# working.net
KiCad netlist of a schematic drawn in EAGLE
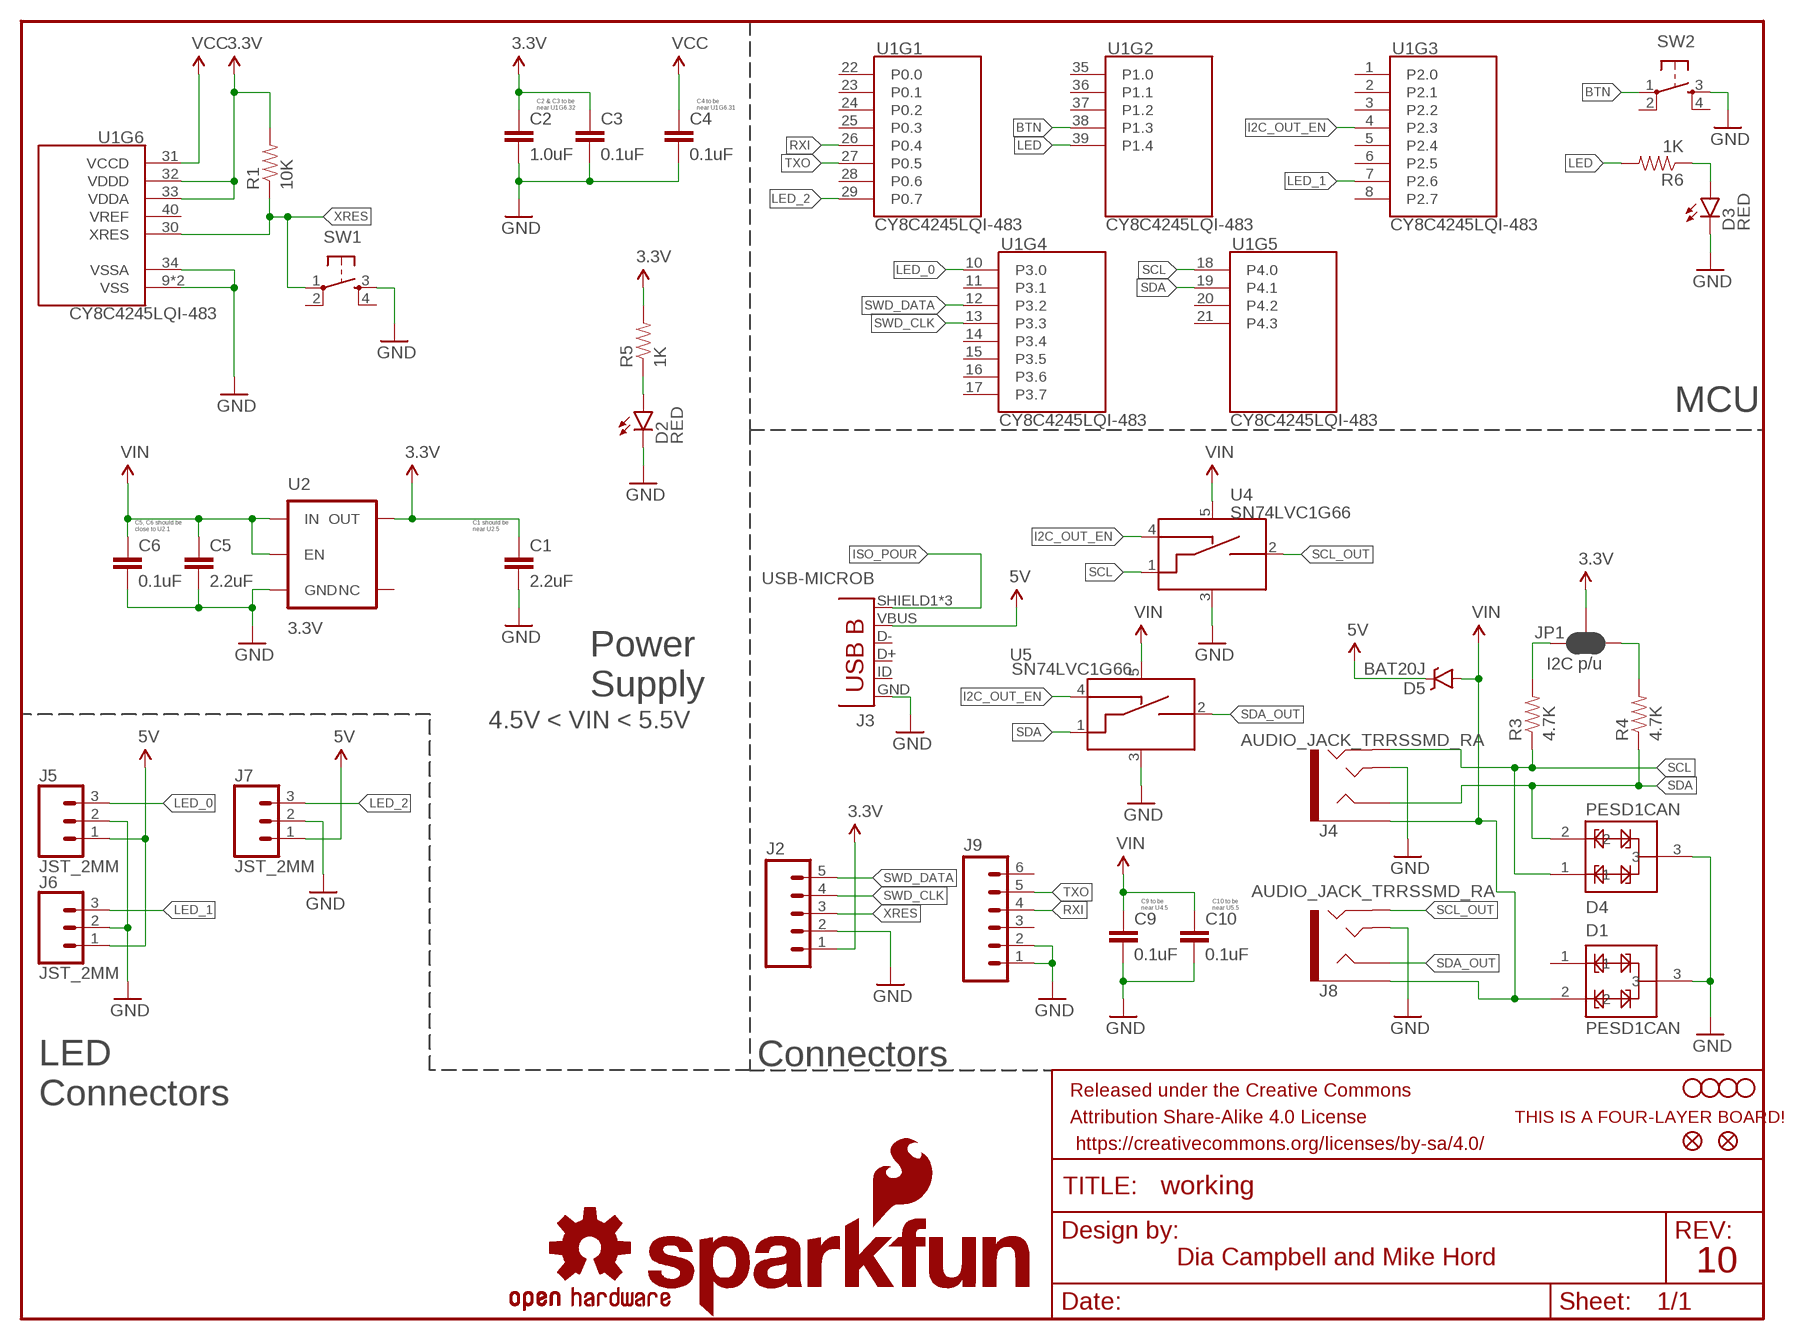
[diagram p0: schematic, sheet 1]

(export (version "E")
  (design (tool "Eeschema 10.0.6"))
  (components
    (comp (ref "C1")
      (value "2.2uF")
      (footprint "eagle-import:0603-CAP")
      (libsource (lib "eagle-import") (part "2.2UF-10V-20%(0603)"))
    )
    (comp (ref "C2")
      (value "1.0uF")
      (footprint "eagle-import:0402-CAP")
      (libsource (lib "eagle-import") (part "1.0UF-16V-10%(0402)"))
    )
    (comp (ref "C3")
      (value "0.1uF")
      (footprint "eagle-import:0402-CAP")
      (libsource (lib "eagle-import") (part "0.1UF-16V(+-10%)(0402)"))
    )
    (comp (ref "C4")
      (value "0.1uF")
      (footprint "eagle-import:0402-CAP")
      (libsource (lib "eagle-import") (part "0.1UF-16V(+-10%)(0402)"))
    )
    (comp (ref "C5")
      (value "2.2uF")
      (footprint "eagle-import:0603-CAP")
      (libsource (lib "eagle-import") (part "2.2UF-10V-20%(0603)"))
    )
    (comp (ref "C6")
      (value "0.1uF")
      (footprint "eagle-import:0402-CAP")
      (libsource (lib "eagle-import") (part "0.1UF-16V(+-10%)(0402)"))
    )
    (comp (ref "C9")
      (value "0.1uF")
      (footprint "eagle-import:0402-CAP")
      (libsource (lib "eagle-import") (part "0.1UF-16V(+-10%)(0402)"))
    )
    (comp (ref "C10")
      (value "0.1uF")
      (footprint "eagle-import:0402-CAP")
      (libsource (lib "eagle-import") (part "0.1UF-16V(+-10%)(0402)"))
    )
    (comp (ref "D1")
      (value "PESD1CAN")
      (footprint "eagle-import:SOT23-3")
      (libsource (lib "eagle-import") (part "PESD1CAN"))
    )
    (comp (ref "D2")
      (value "RED")
      (footprint "eagle-import:LED-0603")
      (libsource (lib "eagle-import") (part "LED-RED0603"))
    )
    (comp (ref "D3")
      (value "RED")
      (footprint "eagle-import:LED-0603")
      (libsource (lib "eagle-import") (part "LED-RED0603"))
    )
    (comp (ref "D4")
      (value "PESD1CAN")
      (footprint "eagle-import:SOT23-3")
      (libsource (lib "eagle-import") (part "PESD1CAN"))
    )
    (comp (ref "D5")
      (value "BAT20J")
      (footprint "eagle-import:SOD-323")
      (libsource (lib "eagle-import") (part "DIODE-SCHOTTKY-BAT20J"))
    )
    (comp (ref "FD1")
      (value "FIDUCIALUFIDUCIAL")
      (footprint "eagle-import:MICRO-FIDUCIAL")
      (libsource (lib "eagle-import") (part "FIDUCIALUFIDUCIAL"))
    )
    (comp (ref "FD2")
      (value "FIDUCIALUFIDUCIAL")
      (footprint "eagle-import:MICRO-FIDUCIAL")
      (libsource (lib "eagle-import") (part "FIDUCIALUFIDUCIAL"))
    )
    (comp (ref "FRAME1")
      (value "FRAME-LETTER")
      (footprint "eagle-import:CREATIVE_COMMONS")
      (libsource (lib "eagle-import") (part "FRAME-LETTER"))
    )
    (comp (ref "H1")
      (value "STAND-OFF")
      (footprint "eagle-import:STAND-OFF")
      (libsource (lib "eagle-import") (part "STAND-OFF"))
    )
    (comp (ref "H2")
      (value "STAND-OFF")
      (footprint "eagle-import:STAND-OFF")
      (libsource (lib "eagle-import") (part "STAND-OFF"))
    )
    (comp (ref "H3")
      (value "STAND-OFF")
      (footprint "eagle-import:STAND-OFF")
      (libsource (lib "eagle-import") (part "STAND-OFF"))
    )
    (comp (ref "H4")
      (value "STAND-OFF")
      (footprint "eagle-import:STAND-OFF")
      (libsource (lib "eagle-import") (part "STAND-OFF"))
    )
    (comp (ref "J2")
      (value "M05NO_SILK")
      (footprint "eagle-import:1X05_NO_SILK")
      (libsource (lib "eagle-import") (part "M05NO_SILK"))
    )
    (comp (ref "J3")
      (value "USB-MICROB")
      (footprint "eagle-import:USB-B-MICRO-SMD_V03")
      (libsource (lib "eagle-import") (part "USB-MICROB{dblquote}"))
    )
    (comp (ref "J4")
      (value "AUDIO_JACK_TRRSSMD_RA")
      (footprint "eagle-import:AUDIO_JACK_3.5MM_TRRS_SMD_RA")
      (libsource (lib "eagle-import") (part "AUDIO_JACK_TRRSSMD_RA"))
    )
    (comp (ref "J5")
      (value "JST_2MM")
      (footprint "eagle-import:JST-3-PTH-VERT")
      (fields (field (name "PROD_ID") "CONN-13230"))
      (libsource (lib "eagle-import") (part "CONN_03JST-PTH-VERT"))
    )
    (comp (ref "J6")
      (value "JST_2MM")
      (footprint "eagle-import:JST-3-PTH-VERT")
      (fields (field (name "PROD_ID") "CONN-13230"))
      (libsource (lib "eagle-import") (part "CONN_03JST-PTH-VERT"))
    )
    (comp (ref "J7")
      (value "JST_2MM")
      (footprint "eagle-import:JST-3-PTH-VERT")
      (fields (field (name "PROD_ID") "CONN-13230"))
      (libsource (lib "eagle-import") (part "CONN_03JST-PTH-VERT"))
    )
    (comp (ref "J8")
      (value "AUDIO_JACK_TRRSSMD_RA")
      (footprint "eagle-import:AUDIO_JACK_3.5MM_TRRS_SMD_RA")
      (libsource (lib "eagle-import") (part "AUDIO_JACK_TRRSSMD_RA"))
    )
    (comp (ref "J9")
      (value "M06NO_SILK_NO_POP")
      (footprint "eagle-import:1X06_NO_SILK")
      (libsource (lib "eagle-import") (part "M06NO_SILK_NO_POP"))
    )
    (comp (ref "JP1")
      (value "JUMPER-PAD-3-NC_BY_PASTE")
      (footprint "eagle-import:PAD-JUMPER-3-NC_BY_PASTE_YES_SILK_FULL_BOX")
      (libsource (lib "eagle-import") (part "JUMPER-PAD-3-NC_BY_PASTE"))
    )
    (comp (ref "LOGO1")
      (value "OSHW-LOGOS")
      (footprint "eagle-import:OSHW-LOGO-S")
      (libsource (lib "eagle-import") (part "OSHW-LOGOS"))
    )
    (comp (ref "LOGO2")
      (value "SFE_LOGO_NAME_FLAME.1_INCH")
      (footprint "eagle-import:SFE_LOGO_NAME_FLAME_.1")
      (libsource (lib "eagle-import") (part "SFE_LOGO_NAME_FLAME.1_INCH"))
    )
    (comp (ref "R1")
      (value "10K")
      (footprint "eagle-import:0603-RES")
      (libsource (lib "eagle-import") (part "10KOHM-1/10W-1%(0603)0603"))
    )
    (comp (ref "R3")
      (value "4.7K")
      (footprint "eagle-import:0603-RES")
      (libsource (lib "eagle-import") (part "4.7KOHM-1/10W-1%(0603)"))
    )
    (comp (ref "R4")
      (value "4.7K")
      (footprint "eagle-import:0603-RES")
      (libsource (lib "eagle-import") (part "4.7KOHM-1/10W-1%(0603)"))
    )
    (comp (ref "R5")
      (value "1K")
      (footprint "eagle-import:0603-RES")
      (libsource (lib "eagle-import") (part "1KOHM-1/10W-1%(0603)"))
    )
    (comp (ref "R6")
      (value "1K")
      (footprint "eagle-import:0603-RES")
      (libsource (lib "eagle-import") (part "1KOHM-1/10W-1%(0603)"))
    )
    (comp (ref "SW1")
      (value "SWITCH_SPST_4_PINRECT")
      (footprint "eagle-import:TACTILE_SWITCH_SMD_4.6X2.8MM")
      (libsource (lib "eagle-import") (part "SWITCH_SPST_4_PINRECT"))
    )
    (comp (ref "SW2")
      (value "SWITCH_SPST_4_PINRECT")
      (footprint "eagle-import:TACTILE_SWITCH_SMD_4.6X2.8MM")
      (libsource (lib "eagle-import") (part "SWITCH_SPST_4_PINRECT"))
    )
    (comp (ref "U$1")
      (value "FOUR_LAYER_WARNING")
      (footprint "eagle-import:FOUR_LAYER_WARNING")
      (libsource (lib "eagle-import") (part "FOUR_LAYER_WARNING"))
    )
    (comp (ref "U1")
      (value "CY8C4245LQI-483")
      (footprint "eagle-import:QFN-40")
      (libsource (lib "eagle-import") (part "PSOC4_4200_40QFN"))
    )
    (comp (ref "U2")
      (value "3.3V")
      (footprint "eagle-import:SOT23-5")
      (libsource (lib "eagle-import") (part "V_REG_AP2112K-3.3V"))
    )
    (comp (ref "U4")
      (value "SN74LVC1G66")
      (footprint "eagle-import:SOT23-5")
      (libsource (lib "eagle-import") (part "SN74LVC1G66_SPST_AMUX"))
    )
    (comp (ref "U5")
      (value "SN74LVC1G66")
      (footprint "eagle-import:SOT23-5")
      (libsource (lib "eagle-import") (part "SN74LVC1G66_SPST_AMUX"))
    )
  )
  (nets
    (net (code "1") (name "3.3V") (class "Default")
      (node (ref "C1") (pin "1") (pinfunction "1_1") (pintype "passive"))
      (node (ref "C2") (pin "1") (pinfunction "1_1") (pintype "passive"))
      (node (ref "C3") (pin "1") (pinfunction "1_1") (pintype "passive"))
      (node (ref "J2") (pin "1") (pinfunction "1_1") (pintype "passive"))
      (node (ref "JP1") (pin "2") (pinfunction "2_2") (pintype "passive"))
      (node (ref "R1") (pin "2") (pinfunction "2_2") (pintype "passive"))
      (node (ref "R5") (pin "2") (pinfunction "2_2") (pintype "passive"))
      (node (ref "U1") (pin "32") (pinfunction "VDDD_32") (pintype "bidirectional"))
      (node (ref "U1") (pin "33") (pinfunction "VDDA_33") (pintype "bidirectional"))
      (node (ref "U2") (pin "5") (pinfunction "OUT_5") (pintype "passive"))
    )
    (net (code "2") (name "5V") (class "Default")
      (node (ref "D5") (pin "C") (pinfunction "C_C") (pintype "passive"))
      (node (ref "J3") (pin "VBUS") (pinfunction "VBUS_VBUS") (pintype "bidirectional"))
      (node (ref "J5") (pin "1") (pinfunction "1_1") (pintype "passive"))
      (node (ref "J6") (pin "1") (pinfunction "1_1") (pintype "passive"))
      (node (ref "J7") (pin "1") (pinfunction "1_1") (pintype "passive"))
    )
    (net (code "3") (name "BTN") (class "Default")
      (node (ref "SW2") (pin "1") (pinfunction "1_1") (pintype "passive"))
      (node (ref "U1") (pin "38") (pinfunction "P1.3_38") (pintype "bidirectional"))
    )
    (net (code "4") (name "GND") (class "Default")
      (node (ref "C1") (pin "2") (pinfunction "2_2") (pintype "passive"))
      (node (ref "C10") (pin "2") (pinfunction "2_2") (pintype "passive"))
      (node (ref "C2") (pin "2") (pinfunction "2_2") (pintype "passive"))
      (node (ref "C3") (pin "2") (pinfunction "2_2") (pintype "passive"))
      (node (ref "C4") (pin "2") (pinfunction "2_2") (pintype "passive"))
      (node (ref "C5") (pin "2") (pinfunction "2_2") (pintype "passive"))
      (node (ref "C6") (pin "2") (pinfunction "2_2") (pintype "passive"))
      (node (ref "C9") (pin "2") (pinfunction "2_2") (pintype "passive"))
      (node (ref "D1") (pin "3") (pinfunction "3_3") (pintype "bidirectional"))
      (node (ref "D2") (pin "C") (pinfunction "C_C") (pintype "passive"))
      (node (ref "D3") (pin "C") (pinfunction "C_C") (pintype "passive"))
      (node (ref "D4") (pin "3") (pinfunction "3_3") (pintype "bidirectional"))
      (node (ref "J2") (pin "2") (pinfunction "2_2") (pintype "passive"))
      (node (ref "J3") (pin "GND") (pinfunction "GND_GND") (pintype "bidirectional"))
      (node (ref "J4") (pin "TIP") (pinfunction "TIP_TIP") (pintype "bidirectional"))
      (node (ref "J5") (pin "2") (pinfunction "2_2") (pintype "passive"))
      (node (ref "J6") (pin "2") (pinfunction "2_2") (pintype "passive"))
      (node (ref "J7") (pin "2") (pinfunction "2_2") (pintype "passive"))
      (node (ref "J8") (pin "TIP") (pinfunction "TIP_TIP") (pintype "bidirectional"))
      (node (ref "J9") (pin "1") (pinfunction "1_1") (pintype "passive"))
      (node (ref "J9") (pin "2") (pinfunction "2_2") (pintype "passive"))
      (node (ref "SW1") (pin "3") (pinfunction "3_3") (pintype "passive"))
      (node (ref "SW2") (pin "3") (pinfunction "3_3") (pintype "passive"))
      (node (ref "U1") (pin "34") (pinfunction "VSSA_34") (pintype "bidirectional"))
      (node (ref "U1") (pin "9") (pinfunction "VSS_9") (pintype "bidirectional"))
      (node (ref "U1") (pin "EP") (pinfunction "VSS_EP") (pintype "bidirectional"))
      (node (ref "U2") (pin "2") (pinfunction "GND_2") (pintype "input"))
      (node (ref "U4") (pin "3") (pinfunction "VSS_3") (pintype "bidirectional"))
      (node (ref "U5") (pin "3") (pinfunction "VSS_3") (pintype "bidirectional"))
    )
    (net (code "5") (name "I2C_OUT_EN") (class "Default")
      (node (ref "U1") (pin "4") (pinfunction "P2.3_4") (pintype "bidirectional"))
      (node (ref "U4") (pin "4") (pinfunction "CTRL_IN_4") (pintype "bidirectional"))
      (node (ref "U5") (pin "4") (pinfunction "CTRL_IN_4") (pintype "bidirectional"))
    )
    (net (code "6") (name "ISO_POUR") (class "Default")
      (node (ref "J3") (pin "SHIELD1") (pinfunction "SHIELD_SHIELD1") (pintype "bidirectional"))
      (node (ref "J3") (pin "SHIELD2") (pinfunction "SHIELD_SHIELD2") (pintype "bidirectional"))
      (node (ref "J3") (pin "SHIELD3") (pinfunction "SHIELD_SHIELD3") (pintype "bidirectional"))
    )
    (net (code "7") (name "LED") (class "Default")
      (node (ref "R6") (pin "2") (pinfunction "2_2") (pintype "passive"))
      (node (ref "U1") (pin "39") (pinfunction "P1.4_39") (pintype "bidirectional"))
    )
    (net (code "8") (name "LED_0") (class "Default")
      (node (ref "J5") (pin "3") (pinfunction "3_3") (pintype "passive"))
      (node (ref "U1") (pin "10") (pinfunction "P3.0_10") (pintype "bidirectional"))
    )
    (net (code "9") (name "LED_1") (class "Default")
      (node (ref "J6") (pin "3") (pinfunction "3_3") (pintype "passive"))
      (node (ref "U1") (pin "7") (pinfunction "P2.6_7") (pintype "bidirectional"))
    )
    (net (code "10") (name "LED_2") (class "Default")
      (node (ref "J7") (pin "3") (pinfunction "3_3") (pintype "passive"))
      (node (ref "U1") (pin "29") (pinfunction "P0.7_29") (pintype "bidirectional"))
    )
    (net (code "11") (name "Net-(D2-PadA)") (class "Default")
      (node (ref "D2") (pin "A") (pinfunction "A_A") (pintype "passive"))
      (node (ref "R5") (pin "1") (pinfunction "1_1") (pintype "passive"))
    )
    (net (code "12") (name "Net-(D3-PadA)") (class "Default")
      (node (ref "D3") (pin "A") (pinfunction "A_A") (pintype "passive"))
      (node (ref "R6") (pin "1") (pinfunction "1_1") (pintype "passive"))
    )
    (net (code "13") (name "Net-(JP1-Pad1)") (class "Default")
      (node (ref "JP1") (pin "1") (pinfunction "1_1") (pintype "passive"))
      (node (ref "R4") (pin "2") (pinfunction "2_2") (pintype "passive"))
    )
    (net (code "14") (name "Net-(JP1-Pad3)") (class "Default")
      (node (ref "JP1") (pin "3") (pinfunction "3_3") (pintype "passive"))
      (node (ref "R3") (pin "2") (pinfunction "2_2") (pintype "passive"))
    )
    (net (code "15") (name "RXI") (class "Default")
      (node (ref "J9") (pin "4") (pinfunction "4_4") (pintype "passive"))
      (node (ref "U1") (pin "26") (pinfunction "P0.4_26") (pintype "bidirectional"))
    )
    (net (code "16") (name "SCL") (class "Default")
      (node (ref "D4") (pin "1") (pinfunction "1_1") (pintype "bidirectional"))
      (node (ref "J4") (pin "RING2") (pinfunction "RING2_RING2") (pintype "bidirectional"))
      (node (ref "R3") (pin "1") (pinfunction "1_1") (pintype "passive"))
      (node (ref "U1") (pin "18") (pinfunction "P4.0_18") (pintype "bidirectional"))
      (node (ref "U4") (pin "1") (pinfunction "A_IN_1") (pintype "bidirectional"))
    )
    (net (code "17") (name "SCL_OUT") (class "Default")
      (node (ref "J8") (pin "RING2") (pinfunction "RING2_RING2") (pintype "bidirectional"))
      (node (ref "U4") (pin "2") (pinfunction "A_OUT_2") (pintype "bidirectional"))
    )
    (net (code "18") (name "SDA") (class "Default")
      (node (ref "D4") (pin "2") (pinfunction "2_2") (pintype "bidirectional"))
      (node (ref "J4") (pin "RING1") (pinfunction "RING1_RING1") (pintype "bidirectional"))
      (node (ref "R4") (pin "1") (pinfunction "1_1") (pintype "passive"))
      (node (ref "U1") (pin "19") (pinfunction "P4.1_19") (pintype "bidirectional"))
      (node (ref "U5") (pin "1") (pinfunction "A_IN_1") (pintype "bidirectional"))
    )
    (net (code "19") (name "SDA_OUT") (class "Default")
      (node (ref "J8") (pin "RING1") (pinfunction "RING1_RING1") (pintype "bidirectional"))
      (node (ref "U5") (pin "2") (pinfunction "A_OUT_2") (pintype "bidirectional"))
    )
    (net (code "20") (name "SWD_CLK") (class "Default")
      (node (ref "J2") (pin "4") (pinfunction "4_4") (pintype "passive"))
      (node (ref "U1") (pin "13") (pinfunction "P3.3_13") (pintype "bidirectional"))
    )
    (net (code "21") (name "SWD_DATA") (class "Default")
      (node (ref "J2") (pin "5") (pinfunction "5_5") (pintype "passive"))
      (node (ref "U1") (pin "12") (pinfunction "P3.2_12") (pintype "bidirectional"))
    )
    (net (code "22") (name "TXO") (class "Default")
      (node (ref "J9") (pin "5") (pinfunction "5_5") (pintype "passive"))
      (node (ref "U1") (pin "27") (pinfunction "P0.5_27") (pintype "bidirectional"))
    )
    (net (code "23") (name "VCC") (class "Default")
      (node (ref "C4") (pin "1") (pinfunction "1_1") (pintype "passive"))
      (node (ref "U1") (pin "31") (pinfunction "VCCD_31") (pintype "bidirectional"))
    )
    (net (code "24") (name "VIN") (class "Default")
      (node (ref "C10") (pin "1") (pinfunction "1_1") (pintype "passive"))
      (node (ref "C5") (pin "1") (pinfunction "1_1") (pintype "passive"))
      (node (ref "C6") (pin "1") (pinfunction "1_1") (pintype "passive"))
      (node (ref "C9") (pin "1") (pinfunction "1_1") (pintype "passive"))
      (node (ref "D1") (pin "2") (pinfunction "2_2") (pintype "bidirectional"))
      (node (ref "D5") (pin "A") (pinfunction "A_A") (pintype "passive"))
      (node (ref "J4") (pin "EARTH") (pinfunction "EARTH_EARTH") (pintype "bidirectional"))
      (node (ref "J8") (pin "EARTH") (pinfunction "EARTH_EARTH") (pintype "bidirectional"))
      (node (ref "U2") (pin "1") (pinfunction "IN_1") (pintype "input"))
      (node (ref "U2") (pin "3") (pinfunction "EN_3") (pintype "input"))
      (node (ref "U4") (pin "5") (pinfunction "VCC_5") (pintype "bidirectional"))
      (node (ref "U5") (pin "5") (pinfunction "VCC_5") (pintype "bidirectional"))
    )
    (net (code "25") (name "XRES") (class "Default")
      (node (ref "J2") (pin "3") (pinfunction "3_3") (pintype "passive"))
      (node (ref "R1") (pin "1") (pinfunction "1_1") (pintype "passive"))
      (node (ref "SW1") (pin "1") (pinfunction "1_1") (pintype "passive"))
      (node (ref "U1") (pin "30") (pinfunction "XRES_30") (pintype "bidirectional"))
    )
    (net (code "26") (name "unconnected-(D1-Pad1)") (class "Default")
      (node (ref "D1") (pin "1") (pinfunction "1_1") (pintype "bidirectional"))
    )
    (net (code "27") (name "unconnected-(J3-PadD+)") (class "Default")
      (node (ref "J3") (pin "D+") (pinfunction "D+_D+") (pintype "bidirectional"))
    )
    (net (code "28") (name "unconnected-(J3-PadD-)") (class "Default")
      (node (ref "J3") (pin "D-") (pinfunction "D-_D-") (pintype "bidirectional"))
    )
    (net (code "29") (name "unconnected-(J3-USBID-PadID)") (class "Default")
      (node (ref "J3") (pin "ID") (pinfunction "USBID_ID") (pintype "bidirectional"))
    )
    (net (code "30") (name "unconnected-(J9-Pad3)") (class "Default")
      (node (ref "J9") (pin "3") (pinfunction "3_3") (pintype "passive"))
    )
    (net (code "31") (name "unconnected-(J9-Pad6)") (class "Default")
      (node (ref "J9") (pin "6") (pinfunction "6_6") (pintype "passive"))
    )
    (net (code "32") (name "unconnected-(SW1-Pad2)") (class "Default")
      (node (ref "SW1") (pin "2") (pinfunction "2_2") (pintype "passive"))
    )
    (net (code "33") (name "unconnected-(SW1-Pad4)") (class "Default")
      (node (ref "SW1") (pin "4") (pinfunction "4_4") (pintype "passive"))
    )
    (net (code "34") (name "unconnected-(SW2-Pad2)") (class "Default")
      (node (ref "SW2") (pin "2") (pinfunction "2_2") (pintype "passive"))
    )
    (net (code "35") (name "unconnected-(SW2-Pad4)") (class "Default")
      (node (ref "SW2") (pin "4") (pinfunction "4_4") (pintype "passive"))
    )
    (net (code "36") (name "unconnected-(U1A-P0.0-Pad22)") (class "Default")
      (node (ref "U1") (pin "22") (pinfunction "P0.0_22") (pintype "bidirectional"))
    )
    (net (code "37") (name "unconnected-(U1A-P0.1-Pad23)") (class "Default")
      (node (ref "U1") (pin "23") (pinfunction "P0.1_23") (pintype "bidirectional"))
    )
    (net (code "38") (name "unconnected-(U1A-P0.2-Pad24)") (class "Default")
      (node (ref "U1") (pin "24") (pinfunction "P0.2_24") (pintype "bidirectional"))
    )
    (net (code "39") (name "unconnected-(U1A-P0.3-Pad25)") (class "Default")
      (node (ref "U1") (pin "25") (pinfunction "P0.3_25") (pintype "bidirectional"))
    )
    (net (code "40") (name "unconnected-(U1A-P0.6-Pad28)") (class "Default")
      (node (ref "U1") (pin "28") (pinfunction "P0.6_28") (pintype "bidirectional"))
    )
    (net (code "41") (name "unconnected-(U1B-P1.0-Pad35)") (class "Default")
      (node (ref "U1") (pin "35") (pinfunction "P1.0_35") (pintype "bidirectional"))
    )
    (net (code "42") (name "unconnected-(U1B-P1.1-Pad36)") (class "Default")
      (node (ref "U1") (pin "36") (pinfunction "P1.1_36") (pintype "bidirectional"))
    )
    (net (code "43") (name "unconnected-(U1B-P1.2-Pad37)") (class "Default")
      (node (ref "U1") (pin "37") (pinfunction "P1.2_37") (pintype "bidirectional"))
    )
    (net (code "44") (name "unconnected-(U1C-P2.0-Pad1)") (class "Default")
      (node (ref "U1") (pin "1") (pinfunction "P2.0_1") (pintype "bidirectional"))
    )
    (net (code "45") (name "unconnected-(U1C-P2.1-Pad2)") (class "Default")
      (node (ref "U1") (pin "2") (pinfunction "P2.1_2") (pintype "bidirectional"))
    )
    (net (code "46") (name "unconnected-(U1C-P2.2-Pad3)") (class "Default")
      (node (ref "U1") (pin "3") (pinfunction "P2.2_3") (pintype "bidirectional"))
    )
    (net (code "47") (name "unconnected-(U1C-P2.4-Pad5)") (class "Default")
      (node (ref "U1") (pin "5") (pinfunction "P2.4_5") (pintype "bidirectional"))
    )
    (net (code "48") (name "unconnected-(U1C-P2.5-Pad6)") (class "Default")
      (node (ref "U1") (pin "6") (pinfunction "P2.5_6") (pintype "bidirectional"))
    )
    (net (code "49") (name "unconnected-(U1C-P2.7-Pad8)") (class "Default")
      (node (ref "U1") (pin "8") (pinfunction "P2.7_8") (pintype "bidirectional"))
    )
    (net (code "50") (name "unconnected-(U1D-P3.1-Pad11)") (class "Default")
      (node (ref "U1") (pin "11") (pinfunction "P3.1_11") (pintype "bidirectional"))
    )
    (net (code "51") (name "unconnected-(U1D-P3.4-Pad14)") (class "Default")
      (node (ref "U1") (pin "14") (pinfunction "P3.4_14") (pintype "bidirectional"))
    )
    (net (code "52") (name "unconnected-(U1D-P3.5-Pad15)") (class "Default")
      (node (ref "U1") (pin "15") (pinfunction "P3.5_15") (pintype "bidirectional"))
    )
    (net (code "53") (name "unconnected-(U1D-P3.6-Pad16)") (class "Default")
      (node (ref "U1") (pin "16") (pinfunction "P3.6_16") (pintype "bidirectional"))
    )
    (net (code "54") (name "unconnected-(U1D-P3.7-Pad17)") (class "Default")
      (node (ref "U1") (pin "17") (pinfunction "P3.7_17") (pintype "bidirectional"))
    )
    (net (code "55") (name "unconnected-(U1E-P4.2-Pad20)") (class "Default")
      (node (ref "U1") (pin "20") (pinfunction "P4.2_20") (pintype "bidirectional"))
    )
    (net (code "56") (name "unconnected-(U1E-P4.3-Pad21)") (class "Default")
      (node (ref "U1") (pin "21") (pinfunction "P4.3_21") (pintype "bidirectional"))
    )
    (net (code "57") (name "unconnected-(U1F-VREF-Pad40)") (class "Default")
      (node (ref "U1") (pin "40") (pinfunction "VREF_40") (pintype "bidirectional"))
    )
    (net (code "58") (name "unconnected-(U2-NC-Pad4)") (class "Default")
      (node (ref "U2") (pin "4") (pinfunction "NC_4") (pintype "input"))
    )
  )
)
